# Kodi_Remote.net
KiCad netlist of a schematic drawn in EAGLE
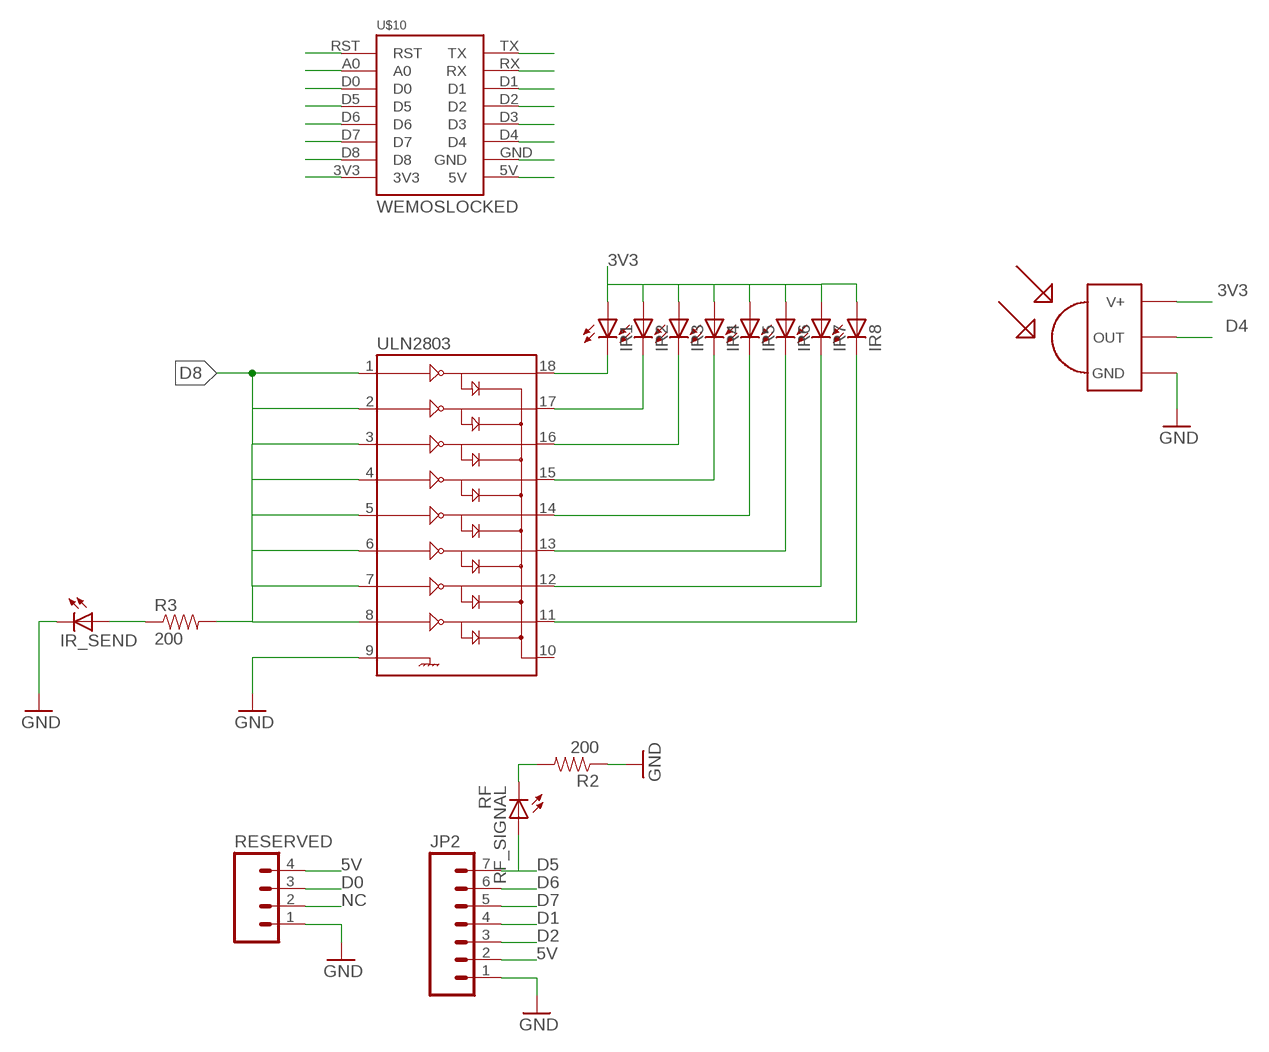
[diagram p0: schematic, sheet 1]

(export (version "E")
  (design (tool "Eeschema 10.0.6"))
  (components
    (comp (ref "IR1")
      (value "LED5MM")
      (footprint "eagle-import:LED5MM")
      (libsource (lib "eagle-import") (part "LED5MM"))
    )
    (comp (ref "IR2")
      (value "LED5MM")
      (footprint "eagle-import:LED5MM")
      (libsource (lib "eagle-import") (part "LED5MM"))
    )
    (comp (ref "IR3")
      (value "LED5MM")
      (footprint "eagle-import:LED5MM")
      (libsource (lib "eagle-import") (part "LED5MM"))
    )
    (comp (ref "IR4")
      (value "LED5MM")
      (footprint "eagle-import:LED5MM")
      (libsource (lib "eagle-import") (part "LED5MM"))
    )
    (comp (ref "IR5")
      (value "LED5MM")
      (footprint "eagle-import:LED5MM")
      (libsource (lib "eagle-import") (part "LED5MM"))
    )
    (comp (ref "IR6")
      (value "LED5MM")
      (footprint "eagle-import:LED5MM")
      (libsource (lib "eagle-import") (part "LED5MM"))
    )
    (comp (ref "IR7")
      (value "LED5MM")
      (footprint "eagle-import:LED5MM")
      (libsource (lib "eagle-import") (part "LED5MM"))
    )
    (comp (ref "IR8")
      (value "LED5MM")
      (footprint "eagle-import:LED5MM")
      (libsource (lib "eagle-import") (part "LED5MM"))
    )
    (comp (ref "IR_SEND")
      (value "LED3MM")
      (footprint "eagle-import:LED3MM")
      (libsource (lib "eagle-import") (part "LED3MM"))
    )
    (comp (ref "JP2")
      (value "M07")
      (footprint "eagle-import:1X07")
      (libsource (lib "eagle-import") (part "M07"))
    )
    (comp (ref "R2")
      (value "200")
      (footprint "eagle-import:0805")
      (libsource (lib "eagle-import") (part "RESISTOR0805-RES"))
    )
    (comp (ref "R3")
      (value "200")
      (footprint "eagle-import:0805")
      (libsource (lib "eagle-import") (part "RESISTOR0805-RES"))
    )
    (comp (ref "RESERVED")
      (value "M04PTH")
      (footprint "eagle-import:1X04")
      (libsource (lib "eagle-import") (part "M04PTH"))
    )
    (comp (ref "RF_SIGNAL")
      (value "RF")
      (footprint "eagle-import:LED3MM")
      (libsource (lib "eagle-import") (part "LED3MM"))
    )
    (comp (ref "TSOP1838")
      (value "TSOP1838")
      (footprint "eagle-import:TSOP18XX")
      (libsource (lib "eagle-import") (part "TSOP1838"))
    )
    (comp (ref "U$10")
      (value "WEMOSLOCKED")
      (footprint "eagle-import:WEMOS_LOCKED")
      (libsource (lib "eagle-import") (part "WEMOSLOCKED"))
    )
    (comp (ref "ULN2803")
      (value "ULN2803DIP")
      (footprint "eagle-import:DIL18")
      (libsource (lib "eagle-import") (part "ULN2803DIP"))
    )
  )
  (nets
    (net (code "1") (name "/3V3") (class "Default")
      (node (ref "IR1") (pin "A") (pinfunction "A_A") (pintype "passive"))
      (node (ref "IR2") (pin "A") (pinfunction "A_A") (pintype "passive"))
      (node (ref "IR3") (pin "A") (pinfunction "A_A") (pintype "passive"))
      (node (ref "IR4") (pin "A") (pinfunction "A_A") (pintype "passive"))
      (node (ref "IR5") (pin "A") (pinfunction "A_A") (pintype "passive"))
      (node (ref "IR6") (pin "A") (pinfunction "A_A") (pintype "passive"))
      (node (ref "IR7") (pin "A") (pinfunction "A_A") (pintype "passive"))
      (node (ref "IR8") (pin "A") (pinfunction "A_A") (pintype "passive"))
      (node (ref "TSOP1838") (pin "VCC") (pinfunction "V+_VCC") (pintype "bidirectional"))
      (node (ref "U$10") (pin "3V3") (pinfunction "3V3_3V3") (pintype "bidirectional"))
    )
    (net (code "2") (name "/5V") (class "Default")
      (node (ref "JP2") (pin "2") (pinfunction "2_2") (pintype "passive"))
      (node (ref "RESERVED") (pin "4") (pinfunction "4_4") (pintype "passive"))
      (node (ref "U$10") (pin "5V") (pinfunction "5V_5V") (pintype "bidirectional"))
    )
    (net (code "3") (name "/D0") (class "Default")
      (node (ref "RESERVED") (pin "3") (pinfunction "3_3") (pintype "passive"))
      (node (ref "U$10") (pin "D0") (pinfunction "D0_D0") (pintype "bidirectional"))
    )
    (net (code "4") (name "/D1") (class "Default")
      (node (ref "JP2") (pin "4") (pinfunction "4_4") (pintype "passive"))
      (node (ref "U$10") (pin "D1") (pinfunction "D1_D1") (pintype "bidirectional"))
    )
    (net (code "5") (name "/D2") (class "Default")
      (node (ref "JP2") (pin "3") (pinfunction "3_3") (pintype "passive"))
      (node (ref "U$10") (pin "D2") (pinfunction "D2_D2") (pintype "bidirectional"))
    )
    (net (code "6") (name "/D4") (class "Default")
      (node (ref "TSOP1838") (pin "OUT") (pinfunction "OUT_OUT") (pintype "bidirectional"))
      (node (ref "U$10") (pin "D4") (pinfunction "D4_D4") (pintype "bidirectional"))
    )
    (net (code "7") (name "/D5") (class "Default")
      (node (ref "JP2") (pin "7") (pinfunction "7_7") (pintype "passive"))
      (node (ref "RF_SIGNAL") (pin "A") (pinfunction "A_A") (pintype "passive"))
      (node (ref "U$10") (pin "D5") (pinfunction "D5_D5") (pintype "bidirectional"))
    )
    (net (code "8") (name "/D6") (class "Default")
      (node (ref "JP2") (pin "6") (pinfunction "6_6") (pintype "passive"))
      (node (ref "U$10") (pin "D6") (pinfunction "D6_D6") (pintype "bidirectional"))
    )
    (net (code "9") (name "/D7") (class "Default")
      (node (ref "JP2") (pin "5") (pinfunction "5_5") (pintype "passive"))
      (node (ref "U$10") (pin "D7") (pinfunction "D7_D7") (pintype "bidirectional"))
    )
    (net (code "10") (name "/NC") (class "Default")
      (node (ref "RESERVED") (pin "2") (pinfunction "2_2") (pintype "passive"))
    )
    (net (code "11") (name "D8") (class "Default")
      (node (ref "R3") (pin "2") (pinfunction "2_2") (pintype "passive"))
      (node (ref "U$10") (pin "D8") (pinfunction "D8_D8") (pintype "bidirectional"))
      (node (ref "ULN2803") (pin "1") (pinfunction "1_1") (pintype "bidirectional"))
      (node (ref "ULN2803") (pin "2") (pinfunction "2_2") (pintype "bidirectional"))
      (node (ref "ULN2803") (pin "3") (pinfunction "3_3") (pintype "bidirectional"))
      (node (ref "ULN2803") (pin "4") (pinfunction "4_4") (pintype "bidirectional"))
      (node (ref "ULN2803") (pin "5") (pinfunction "5_5") (pintype "bidirectional"))
      (node (ref "ULN2803") (pin "6") (pinfunction "6_6") (pintype "bidirectional"))
      (node (ref "ULN2803") (pin "7") (pinfunction "7_7") (pintype "bidirectional"))
      (node (ref "ULN2803") (pin "8") (pinfunction "8_8") (pintype "bidirectional"))
    )
    (net (code "12") (name "GND") (class "Default")
      (node (ref "IR_SEND") (pin "K") (pinfunction "C_K") (pintype "passive"))
      (node (ref "JP2") (pin "1") (pinfunction "1_1") (pintype "passive"))
      (node (ref "R2") (pin "1") (pinfunction "1_1") (pintype "passive"))
      (node (ref "RESERVED") (pin "1") (pinfunction "1_1") (pintype "passive"))
      (node (ref "TSOP1838") (pin "GND") (pinfunction "GND_GND") (pintype "bidirectional"))
      (node (ref "ULN2803") (pin "9") (pinfunction "9_9") (pintype "bidirectional"))
    )
    (net (code "13") (name "Net-(IR1-C)") (class "Default")
      (node (ref "IR1") (pin "K") (pinfunction "C_K") (pintype "passive"))
      (node (ref "ULN2803") (pin "18") (pinfunction "18_18") (pintype "bidirectional"))
    )
    (net (code "14") (name "Net-(IR2-C)") (class "Default")
      (node (ref "IR2") (pin "K") (pinfunction "C_K") (pintype "passive"))
      (node (ref "ULN2803") (pin "17") (pinfunction "17_17") (pintype "bidirectional"))
    )
    (net (code "15") (name "Net-(IR3-C)") (class "Default")
      (node (ref "IR3") (pin "K") (pinfunction "C_K") (pintype "passive"))
      (node (ref "ULN2803") (pin "16") (pinfunction "16_16") (pintype "bidirectional"))
    )
    (net (code "16") (name "Net-(IR4-C)") (class "Default")
      (node (ref "IR4") (pin "K") (pinfunction "C_K") (pintype "passive"))
      (node (ref "ULN2803") (pin "15") (pinfunction "15_15") (pintype "bidirectional"))
    )
    (net (code "17") (name "Net-(IR5-C)") (class "Default")
      (node (ref "IR5") (pin "K") (pinfunction "C_K") (pintype "passive"))
      (node (ref "ULN2803") (pin "14") (pinfunction "14_14") (pintype "bidirectional"))
    )
    (net (code "18") (name "Net-(IR6-C)") (class "Default")
      (node (ref "IR6") (pin "K") (pinfunction "C_K") (pintype "passive"))
      (node (ref "ULN2803") (pin "13") (pinfunction "13_13") (pintype "bidirectional"))
    )
    (net (code "19") (name "Net-(IR7-C)") (class "Default")
      (node (ref "IR7") (pin "K") (pinfunction "C_K") (pintype "passive"))
      (node (ref "ULN2803") (pin "12") (pinfunction "12_12") (pintype "bidirectional"))
    )
    (net (code "20") (name "Net-(IR8-C)") (class "Default")
      (node (ref "IR8") (pin "K") (pinfunction "C_K") (pintype "passive"))
      (node (ref "ULN2803") (pin "11") (pinfunction "11_11") (pintype "bidirectional"))
    )
    (net (code "21") (name "Net-(IR_SEND-PadA)") (class "Default")
      (node (ref "IR_SEND") (pin "A") (pinfunction "A_A") (pintype "passive"))
      (node (ref "R3") (pin "1") (pinfunction "1_1") (pintype "passive"))
    )
    (net (code "22") (name "Net-(RF_SIGNAL-C)") (class "Default")
      (node (ref "R2") (pin "2") (pinfunction "2_2") (pintype "passive"))
      (node (ref "RF_SIGNAL") (pin "K") (pinfunction "C_K") (pintype "passive"))
    )
    (net (code "23") (name "unconnected-(U$10-PadA0)") (class "Default")
      (node (ref "U$10") (pin "A0") (pinfunction "A0_A0") (pintype "bidirectional"))
    )
    (net (code "24") (name "unconnected-(U$10-PadD3)") (class "Default")
      (node (ref "U$10") (pin "D3") (pinfunction "D3_D3") (pintype "bidirectional"))
    )
    (net (code "25") (name "unconnected-(U$10-PadGND)") (class "Default")
      (node (ref "U$10") (pin "GND") (pinfunction "GND_GND") (pintype "bidirectional"))
    )
    (net (code "26") (name "unconnected-(U$10-PadRST)") (class "Default")
      (node (ref "U$10") (pin "RST") (pinfunction "RST_RST") (pintype "bidirectional"))
    )
    (net (code "27") (name "unconnected-(U$10-PadRX)") (class "Default")
      (node (ref "U$10") (pin "RX") (pinfunction "RX_RX") (pintype "bidirectional"))
    )
    (net (code "28") (name "unconnected-(U$10-PadTX)") (class "Default")
      (node (ref "U$10") (pin "TX") (pinfunction "TX_TX") (pintype "bidirectional"))
    )
    (net (code "29") (name "unconnected-(ULN2803-Pad10)") (class "Default")
      (node (ref "ULN2803") (pin "10") (pinfunction "10_10") (pintype "bidirectional"))
    )
  )
)
